# drums.net
KiCad netlist of a schematic drawn in EAGLE
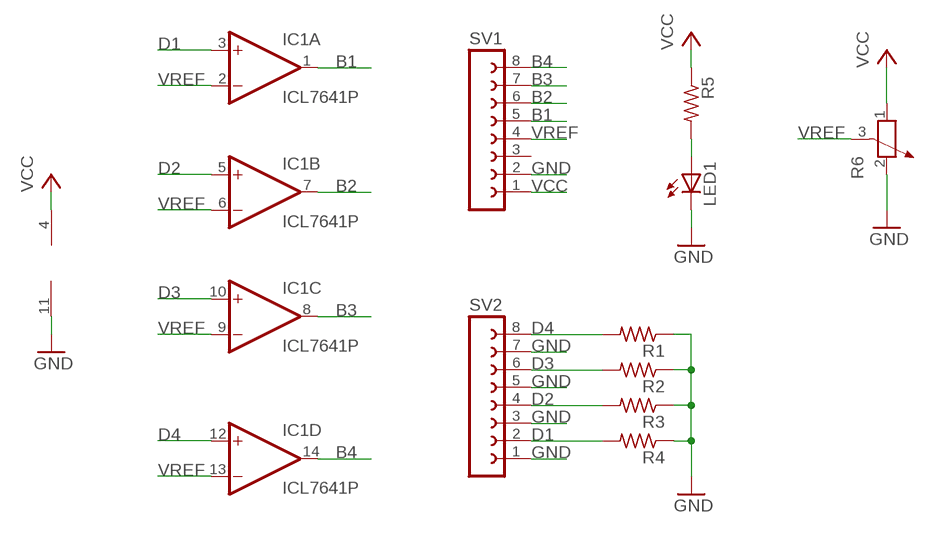
[diagram p0: schematic, sheet 1]

(export (version "E")
  (design (tool "Eeschema 10.0.6"))
  (components
    (comp (ref "IC1")
      (value "ICL7641P")
      (footprint "eagle-import:DIL14")
      (libsource (lib "eagle-import") (part "ICL7641P"))
    )
    (comp (ref "LED1")
      (value "LED5MM")
      (footprint "eagle-import:LED5MM")
      (libsource (lib "eagle-import") (part "LED5MM"))
    )
    (comp (ref "R1")
      (value "R-US_0207/7")
      (footprint "eagle-import:0207_7")
      (libsource (lib "eagle-import") (part "R-US_0207/7"))
    )
    (comp (ref "R2")
      (value "R-US_0207/7")
      (footprint "eagle-import:0207_7")
      (libsource (lib "eagle-import") (part "R-US_0207/7"))
    )
    (comp (ref "R3")
      (value "R-US_0207/7")
      (footprint "eagle-import:0207_7")
      (libsource (lib "eagle-import") (part "R-US_0207/7"))
    )
    (comp (ref "R4")
      (value "R-US_0207/7")
      (footprint "eagle-import:0207_7")
      (libsource (lib "eagle-import") (part "R-US_0207/7"))
    )
    (comp (ref "R5")
      (value "R-US_0207/7")
      (footprint "eagle-import:0207_7")
      (libsource (lib "eagle-import") (part "R-US_0207/7"))
    )
    (comp (ref "R6")
      (value "POTENTIOMETER_PT_SPIN")
      (footprint "eagle-import:PT-SPIN")
      (libsource (lib "eagle-import") (part "POTENTIOMETER_PT_SPIN"))
    )
    (comp (ref "SV1")
      (value "FE08-1")
      (footprint "eagle-import:FE08")
      (libsource (lib "eagle-import") (part "FE08-1"))
    )
    (comp (ref "SV2")
      (value "FE08-1")
      (footprint "eagle-import:FE08")
      (libsource (lib "eagle-import") (part "FE08-1"))
    )
  )
  (nets
    (net (code "1") (name "/B1") (class "Default")
      (node (ref "IC1") (pin "1") (pinfunction "OUT_1") (pintype "output"))
      (node (ref "SV1") (pin "5") (pinfunction "5_5") (pintype "passive"))
    )
    (net (code "2") (name "/B2") (class "Default")
      (node (ref "IC1") (pin "7") (pinfunction "OUT_7") (pintype "output"))
      (node (ref "SV1") (pin "6") (pinfunction "6_6") (pintype "passive"))
    )
    (net (code "3") (name "/B3") (class "Default")
      (node (ref "IC1") (pin "8") (pinfunction "OUT_8") (pintype "output"))
      (node (ref "SV1") (pin "7") (pinfunction "7_7") (pintype "passive"))
    )
    (net (code "4") (name "/B4") (class "Default")
      (node (ref "IC1") (pin "14") (pinfunction "OUT_14") (pintype "output"))
      (node (ref "SV1") (pin "8") (pinfunction "8_8") (pintype "passive"))
    )
    (net (code "5") (name "/D1") (class "Default")
      (node (ref "IC1") (pin "3") (pinfunction "+IN_3") (pintype "input"))
      (node (ref "R4") (pin "2") (pinfunction "2_2") (pintype "passive"))
      (node (ref "SV2") (pin "2") (pinfunction "2_2") (pintype "passive"))
    )
    (net (code "6") (name "/D2") (class "Default")
      (node (ref "IC1") (pin "5") (pinfunction "+IN_5") (pintype "input"))
      (node (ref "R3") (pin "2") (pinfunction "2_2") (pintype "passive"))
      (node (ref "SV2") (pin "4") (pinfunction "4_4") (pintype "passive"))
    )
    (net (code "7") (name "/D3") (class "Default")
      (node (ref "IC1") (pin "10") (pinfunction "+IN_10") (pintype "input"))
      (node (ref "R2") (pin "2") (pinfunction "2_2") (pintype "passive"))
      (node (ref "SV2") (pin "6") (pinfunction "6_6") (pintype "passive"))
    )
    (net (code "8") (name "/D4") (class "Default")
      (node (ref "IC1") (pin "12") (pinfunction "+IN_12") (pintype "input"))
      (node (ref "R1") (pin "2") (pinfunction "2_2") (pintype "passive"))
      (node (ref "SV2") (pin "8") (pinfunction "8_8") (pintype "passive"))
    )
    (net (code "9") (name "/VREF") (class "Default")
      (node (ref "IC1") (pin "13") (pinfunction "-IN_13") (pintype "input"))
      (node (ref "IC1") (pin "2") (pinfunction "-IN_2") (pintype "input"))
      (node (ref "IC1") (pin "6") (pinfunction "-IN_6") (pintype "input"))
      (node (ref "IC1") (pin "9") (pinfunction "-IN_9") (pintype "input"))
      (node (ref "R6") (pin "3") (pinfunction "3_3") (pintype "passive"))
      (node (ref "SV1") (pin "4") (pinfunction "4_4") (pintype "passive"))
    )
    (net (code "10") (name "GND") (class "Default")
      (node (ref "IC1") (pin "11") (pinfunction "V-_11") (pintype "power_in"))
      (node (ref "LED1") (pin "K") (pinfunction "C_K") (pintype "passive"))
      (node (ref "R1") (pin "1") (pinfunction "1_1") (pintype "passive"))
      (node (ref "R2") (pin "1") (pinfunction "1_1") (pintype "passive"))
      (node (ref "R3") (pin "1") (pinfunction "1_1") (pintype "passive"))
      (node (ref "R4") (pin "1") (pinfunction "1_1") (pintype "passive"))
      (node (ref "R6") (pin "2") (pinfunction "2_2") (pintype "passive"))
      (node (ref "SV1") (pin "2") (pinfunction "2_2") (pintype "passive"))
      (node (ref "SV2") (pin "1") (pinfunction "1_1") (pintype "passive"))
      (node (ref "SV2") (pin "3") (pinfunction "3_3") (pintype "passive"))
      (node (ref "SV2") (pin "5") (pinfunction "5_5") (pintype "passive"))
      (node (ref "SV2") (pin "7") (pinfunction "7_7") (pintype "passive"))
    )
    (net (code "11") (name "Net-(LED1-PadA)") (class "Default")
      (node (ref "LED1") (pin "A") (pinfunction "A_A") (pintype "passive"))
      (node (ref "R5") (pin "2") (pinfunction "2_2") (pintype "passive"))
    )
    (net (code "12") (name "VCC") (class "Default")
      (node (ref "IC1") (pin "4") (pinfunction "V+_4") (pintype "power_in"))
      (node (ref "R5") (pin "1") (pinfunction "1_1") (pintype "passive"))
      (node (ref "R6") (pin "1") (pinfunction "1_1") (pintype "passive"))
      (node (ref "SV1") (pin "1") (pinfunction "1_1") (pintype "passive"))
    )
    (net (code "13") (name "unconnected-(SV1-Pad3)") (class "Default")
      (node (ref "SV1") (pin "3") (pinfunction "3_3") (pintype "passive"))
    )
  )
)
